# WIFISocket.net
KiCad netlist of a schematic drawn in Altium Designer
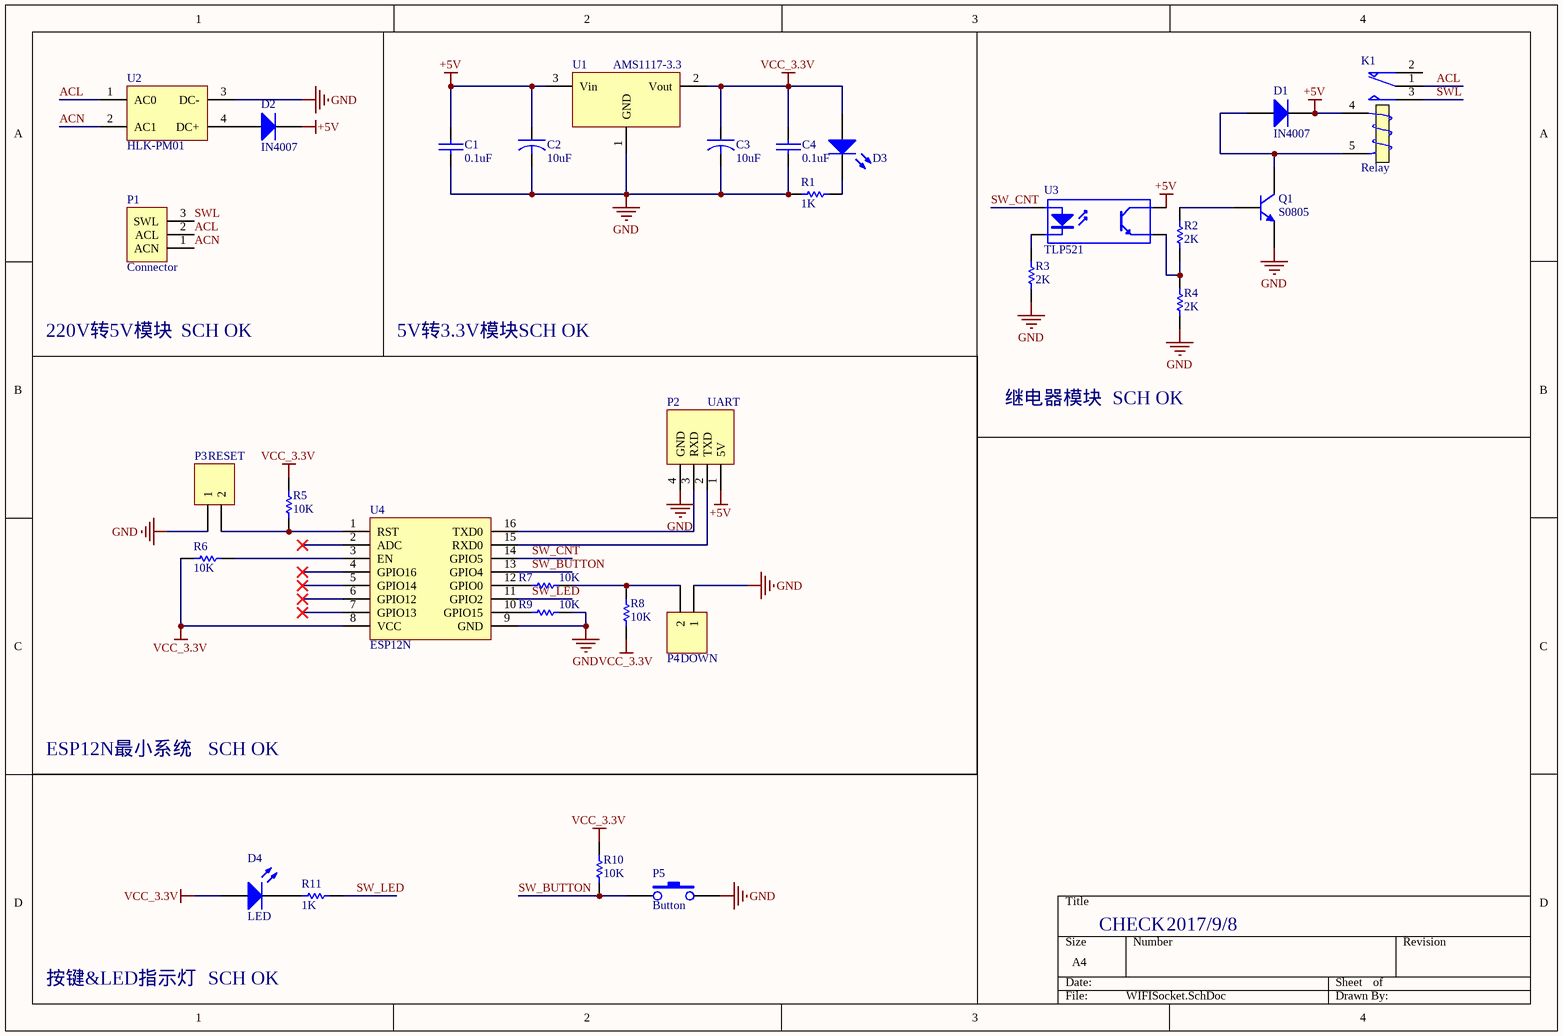
[diagram p0: WIFISocket.SchDoc]

(export (version "E")
  (design (tool "Eeschema 10.0.6"))
  (components
    (comp (ref "C1")
      (value "0.1uF")
      (footprint "0603A")
      (description "Capacitor")
      (libsource (lib "WIFISocket") (part "CAP"))
    )
    (comp (ref "C2")
      (value "10uF")
      (footprint "0603A")
      (description "Capacitor")
      (libsource (lib "WIFISocket") (part "CAPACITOR"))
    )
    (comp (ref "C3")
      (value "10uF")
      (footprint "0603A")
      (description "Capacitor")
      (libsource (lib "WIFISocket") (part "CAPACITOR"))
    )
    (comp (ref "C4")
      (value "0.1uF")
      (footprint "0603A")
      (description "Capacitor")
      (libsource (lib "WIFISocket") (part "CAP"))
    )
    (comp (ref "D1")
      (value "IN4007")
      (footprint "1N4007")
      (description "整流二极管")
      (libsource (lib "WIFISocket") (part "IN4007"))
    )
    (comp (ref "D2")
      (value "IN4007")
      (footprint "1N4007")
      (description "整流二极管")
      (libsource (lib "WIFISocket") (part "IN4007"))
    )
    (comp (ref "D3") (value "LED") (footprint "LED") (libsource (lib "WIFISocket") (part "LED")))
    (comp (ref "D4") (value "LED") (footprint "LED") (libsource (lib "WIFISocket") (part "LED")))
    (comp (ref "K1")
      (value "Relay")
      (footprint "Relay")
      (description "SPDT Relay")
      (libsource (lib "WIFISocket") (part "Relay"))
    )
    (comp (ref "P1")
      (value "Connector")
      (footprint "KF128-3P")
      (description "220V插座焊盘")
      (libsource (lib "WIFISocket") (part "Socket"))
    )
    (comp (ref "P2")
      (value "UART")
      (footprint "HDR1X4")
      (description "UART下载接口")
      (libsource (lib "WIFISocket") (part "UART"))
    )
    (comp (ref "P3")
      (value "RESET")
      (footprint "HDR1X2")
      (description "Header, 2-Pin")
      (libsource (lib "") (part "Header 2_1"))
    )
    (comp (ref "P4")
      (value "DOWN")
      (footprint "HDR1X2")
      (description "Header, 2-Pin")
      (libsource (lib "WIFISocket") (part "Header 2"))
    )
    (comp (ref "P5")
      (value "Button")
      (footprint "BUTTON")
      (description "按键")
      (libsource (lib "WIFISocket") (part "Button"))
    )
    (comp (ref "Q1")
      (value "S0805")
      (footprint "SOT23")
      (description "NPN")
      (libsource (lib "WIFISocket") (part "S0805"))
    )
    (comp (ref "R1")
      (value "1K")
      (footprint "0603R")
      (description "Resistor")
      (fields (field (name "Comment") "Res"))
      (libsource (lib "WIFISocket") (part "Res"))
    )
    (comp (ref "R2")
      (value "2K")
      (footprint "0603R")
      (description "Resistor")
      (fields (field (name "Comment") "Res"))
      (libsource (lib "WIFISocket") (part "Res"))
    )
    (comp (ref "R3")
      (value "2K")
      (footprint "0603R")
      (description "Resistor")
      (fields (field (name "Comment") "Res"))
      (libsource (lib "WIFISocket") (part "Res"))
    )
    (comp (ref "R4")
      (value "2K")
      (footprint "0603R")
      (description "Resistor")
      (fields (field (name "Comment") "Res"))
      (libsource (lib "WIFISocket") (part "Res"))
    )
    (comp (ref "R5")
      (value "10K")
      (footprint "0603R")
      (description "Resistor")
      (fields (field (name "Comment") "Res"))
      (libsource (lib "WIFISocket") (part "Res"))
    )
    (comp (ref "R6")
      (value "10K")
      (footprint "0603R")
      (description "Resistor")
      (fields (field (name "Comment") "Res"))
      (libsource (lib "WIFISocket") (part "Res"))
    )
    (comp (ref "R7")
      (value "10K")
      (footprint "0603R")
      (description "Resistor")
      (fields (field (name "Comment") "Res"))
      (libsource (lib "WIFISocket") (part "Res"))
    )
    (comp (ref "R8")
      (value "10K")
      (footprint "0603R")
      (description "Resistor")
      (fields (field (name "Comment") "Res"))
      (libsource (lib "WIFISocket") (part "Res"))
    )
    (comp (ref "R9")
      (value "10K")
      (footprint "0603R")
      (description "Resistor")
      (fields (field (name "Comment") "Res"))
      (libsource (lib "WIFISocket") (part "Res"))
    )
    (comp (ref "R10")
      (value "10K")
      (footprint "0603R")
      (description "Resistor")
      (fields (field (name "Comment") "Res"))
      (libsource (lib "WIFISocket") (part "Res"))
    )
    (comp (ref "R11")
      (value "1K")
      (footprint "0603R")
      (description "Resistor")
      (fields (field (name "Comment") "Res"))
      (libsource (lib "WIFISocket") (part "Res"))
    )
    (comp (ref "U1")
      (value "AMS1117-3.3")
      (footprint "AMS1117-3.3")
      (description "5V转3V")
      (libsource (lib "WIFISocket") (part "AMS1117-3.3"))
    )
    (comp (ref "U2")
      (value "HLK-PM01")
      (footprint "HLK_PM01")
      (description "220V AC转5V DC模块")
      (libsource (lib "WIFISocket") (part "HLK-PM01"))
    )
    (comp (ref "U3")
      (value "TLP521")
      (footprint "DIP-4")
      (description "光耦")
      (libsource (lib "WIFISocket") (part "Optoisolator"))
    )
    (comp (ref "U4")
      (value "ESP12N")
      (footprint "ESP_12")
      (description "ESP12N无线模块")
      (libsource (lib "WIFISocket") (part "ESP12N"))
    )
  )
  (nets
    (net (code "1") (name "+5V") (class "Default")
      (node (ref "C1") (pin "1") (pinfunction "1_1") (pintype "passive"))
      (node (ref "C2") (pin "1") (pinfunction "1_1") (pintype "passive"))
      (node (ref "D1") (pin "2") (pinfunction "K_2") (pintype "passive"))
      (node (ref "D2") (pin "2") (pinfunction "K_2") (pintype "passive"))
      (node (ref "K1") (pin "4") (pinfunction "T1_4") (pintype "passive"))
      (node (ref "P2") (pin "1") (pinfunction "5V_1") (pintype "passive"))
      (node (ref "U1") (pin "3") (pinfunction "Vin_3") (pintype "passive"))
      (node (ref "U3") (pin "4") (pinfunction "C_4") (pintype "passive"))
    )
    (net (code "2") (name "/ACL") (class "Default")
      (node (ref "K1") (pin "1") (pinfunction "COM_1") (pintype "passive"))
      (node (ref "P1") (pin "2") (pinfunction "ACL_2") (pintype "passive"))
      (node (ref "U2") (pin "1") (pinfunction "AC0_1") (pintype "passive"))
    )
    (net (code "3") (name "/ACN") (class "Default")
      (node (ref "P1") (pin "1") (pinfunction "ACN_1") (pintype "passive"))
      (node (ref "U2") (pin "2") (pinfunction "AC1_2") (pintype "passive"))
    )
    (net (code "4") (name "/SWL") (class "Default")
      (node (ref "K1") (pin "3") (pinfunction "NO_3") (pintype "passive"))
      (node (ref "P1") (pin "3") (pinfunction "SWL_3") (pintype "passive"))
    )
    (net (code "5") (name "/SW_BUTTON") (class "Default")
      (node (ref "P5") (pin "1") (pinfunction "1_1") (pintype "passive"))
      (node (ref "R10") (pin "1") (pinfunction "1_1") (pintype "passive"))
      (node (ref "U4") (pin "13") (pinfunction "GPIO4_13") (pintype "passive"))
    )
    (net (code "6") (name "/SW_CNT") (class "Default")
      (node (ref "U3") (pin "1") (pinfunction "A_1") (pintype "passive"))
      (node (ref "U4") (pin "14") (pinfunction "GPIO5_14") (pintype "passive"))
    )
    (net (code "7") (name "/SW_LED") (class "Default")
      (node (ref "R11") (pin "1") (pinfunction "1_1") (pintype "passive"))
      (node (ref "U4") (pin "11") (pinfunction "GPIO2_11") (pintype "passive"))
    )
    (net (code "8") (name "GND") (class "Default")
      (node (ref "C1") (pin "2") (pinfunction "2_2") (pintype "passive"))
      (node (ref "C2") (pin "2") (pinfunction "2_2") (pintype "passive"))
      (node (ref "C3") (pin "2") (pinfunction "2_2") (pintype "passive"))
      (node (ref "C4") (pin "2") (pinfunction "2_2") (pintype "passive"))
      (node (ref "P2") (pin "4") (pinfunction "GND_4") (pintype "passive"))
      (node (ref "P3") (pin "1") (pinfunction "1_1") (pintype "passive"))
      (node (ref "P4") (pin "1") (pinfunction "1_1") (pintype "passive"))
      (node (ref "P5") (pin "2") (pinfunction "2_2") (pintype "passive"))
      (node (ref "Q1") (pin "E") (pinfunction "E_E") (pintype "passive"))
      (node (ref "R1") (pin "1") (pinfunction "1_1") (pintype "passive"))
      (node (ref "R3") (pin "1") (pinfunction "1_1") (pintype "passive"))
      (node (ref "R4") (pin "1") (pinfunction "1_1") (pintype "passive"))
      (node (ref "R9") (pin "2") (pinfunction "2_2") (pintype "passive"))
      (node (ref "U1") (pin "1") (pinfunction "GND_1") (pintype "passive"))
      (node (ref "U2") (pin "3") (pinfunction "DC-_3") (pintype "passive"))
      (node (ref "U4") (pin "9") (pinfunction "GND_9") (pintype "passive"))
    )
    (net (code "9") (name "Net-(D1-A)") (class "Default")
      (node (ref "D1") (pin "1") (pinfunction "A_1") (pintype "passive"))
      (node (ref "K1") (pin "5") (pinfunction "T2_5") (pintype "passive"))
      (node (ref "Q1") (pin "C") (pinfunction "C_C") (pintype "passive"))
    )
    (net (code "10") (name "Net-(D2-A)") (class "Default")
      (node (ref "D2") (pin "1") (pinfunction "A_1") (pintype "passive"))
      (node (ref "U2") (pin "4") (pinfunction "DC+_4") (pintype "passive"))
    )
    (net (code "11") (name "Net-(D3-K)") (class "Default")
      (node (ref "D3") (pin "2") (pinfunction "K_2") (pintype "passive"))
      (node (ref "R1") (pin "2") (pinfunction "2_2") (pintype "passive"))
    )
    (net (code "12") (name "Net-(D4-K)") (class "Default")
      (node (ref "D4") (pin "2") (pinfunction "K_2") (pintype "passive"))
      (node (ref "R11") (pin "2") (pinfunction "2_2") (pintype "passive"))
    )
    (net (code "13") (name "Net-(P2-RXD)") (class "Default")
      (node (ref "P2") (pin "3") (pinfunction "RXD_3") (pintype "passive"))
      (node (ref "U4") (pin "16") (pinfunction "TXD0_16") (pintype "passive"))
    )
    (net (code "14") (name "Net-(P2-TXD)") (class "Default")
      (node (ref "P2") (pin "2") (pinfunction "TXD_2") (pintype "passive"))
      (node (ref "U4") (pin "15") (pinfunction "RXD0_15") (pintype "passive"))
    )
    (net (code "15") (name "Net-(P4-Pad2)") (class "Default")
      (node (ref "P4") (pin "2") (pinfunction "2_2") (pintype "passive"))
      (node (ref "R7") (pin "2") (pinfunction "2_2") (pintype "passive"))
      (node (ref "R8") (pin "2") (pinfunction "2_2") (pintype "passive"))
    )
    (net (code "16") (name "Net-(Q1-PadB)") (class "Default")
      (node (ref "Q1") (pin "B") (pinfunction "B_B") (pintype "passive"))
      (node (ref "R2") (pin "2") (pinfunction "2_2") (pintype "passive"))
    )
    (net (code "17") (name "Net-(U3-E)") (class "Default")
      (node (ref "R2") (pin "1") (pinfunction "1_1") (pintype "passive"))
      (node (ref "R4") (pin "2") (pinfunction "2_2") (pintype "passive"))
      (node (ref "U3") (pin "3") (pinfunction "E_3") (pintype "passive"))
    )
    (net (code "18") (name "Net-(U3-K)") (class "Default")
      (node (ref "R3") (pin "2") (pinfunction "2_2") (pintype "passive"))
      (node (ref "U3") (pin "2") (pinfunction "K_2") (pintype "passive"))
    )
    (net (code "19") (name "Net-(U4-EN)") (class "Default")
      (node (ref "R6") (pin "2") (pinfunction "2_2") (pintype "passive"))
      (node (ref "U4") (pin "3") (pinfunction "EN_3") (pintype "passive"))
    )
    (net (code "20") (name "Net-(U4-GPIO0)") (class "Default")
      (node (ref "R7") (pin "1") (pinfunction "1_1") (pintype "passive"))
      (node (ref "U4") (pin "12") (pinfunction "GPIO0_12") (pintype "passive"))
    )
    (net (code "21") (name "Net-(U4-GPIO15)") (class "Default")
      (node (ref "R9") (pin "1") (pinfunction "1_1") (pintype "passive"))
      (node (ref "U4") (pin "10") (pinfunction "GPIO15_10") (pintype "passive"))
    )
    (net (code "22") (name "Net-(U4-RST)") (class "Default")
      (node (ref "P3") (pin "2") (pinfunction "2_2") (pintype "passive"))
      (node (ref "R5") (pin "1") (pinfunction "1_1") (pintype "passive"))
      (node (ref "U4") (pin "1") (pinfunction "RST_1") (pintype "passive"))
    )
    (net (code "23") (name "VCC_3.3V") (class "Default")
      (node (ref "C3") (pin "1") (pinfunction "1_1") (pintype "passive"))
      (node (ref "C4") (pin "1") (pinfunction "1_1") (pintype "passive"))
      (node (ref "D3") (pin "1") (pinfunction "A_1") (pintype "passive"))
      (node (ref "D4") (pin "1") (pinfunction "A_1") (pintype "passive"))
      (node (ref "R10") (pin "2") (pinfunction "2_2") (pintype "passive"))
      (node (ref "R5") (pin "2") (pinfunction "2_2") (pintype "passive"))
      (node (ref "R6") (pin "1") (pinfunction "1_1") (pintype "passive"))
      (node (ref "R8") (pin "1") (pinfunction "1_1") (pintype "passive"))
      (node (ref "U1") (pin "2") (pinfunction "Vout_2") (pintype "passive"))
      (node (ref "U4") (pin "8") (pinfunction "VCC_8") (pintype "passive"))
    )
    (net (code "24") (name "unconnected-(K1-NC-Pad2)") (class "Default")
      (node (ref "K1") (pin "2") (pinfunction "NC_2") (pintype "passive"))
    )
    (net (code "25") (name "unconnected-(U4-ADC-Pad2)") (class "Default")
      (node (ref "U4") (pin "2") (pinfunction "ADC_2") (pintype "passive+no_connect"))
    )
    (net (code "26") (name "unconnected-(U4-GPIO12-Pad6)") (class "Default")
      (node (ref "U4") (pin "6") (pinfunction "GPIO12_6") (pintype "passive+no_connect"))
    )
    (net (code "27") (name "unconnected-(U4-GPIO13-Pad7)") (class "Default")
      (node (ref "U4") (pin "7") (pinfunction "GPIO13_7") (pintype "passive+no_connect"))
    )
    (net (code "28") (name "unconnected-(U4-GPIO14-Pad5)") (class "Default")
      (node (ref "U4") (pin "5") (pinfunction "GPIO14_5") (pintype "passive+no_connect"))
    )
    (net (code "29") (name "unconnected-(U4-GPIO16-Pad4)") (class "Default")
      (node (ref "U4") (pin "4") (pinfunction "GPIO16_4") (pintype "passive+no_connect"))
    )
  )
)
